# balanceador_arduino.net
KiCad netlist of a schematic drawn in EAGLE
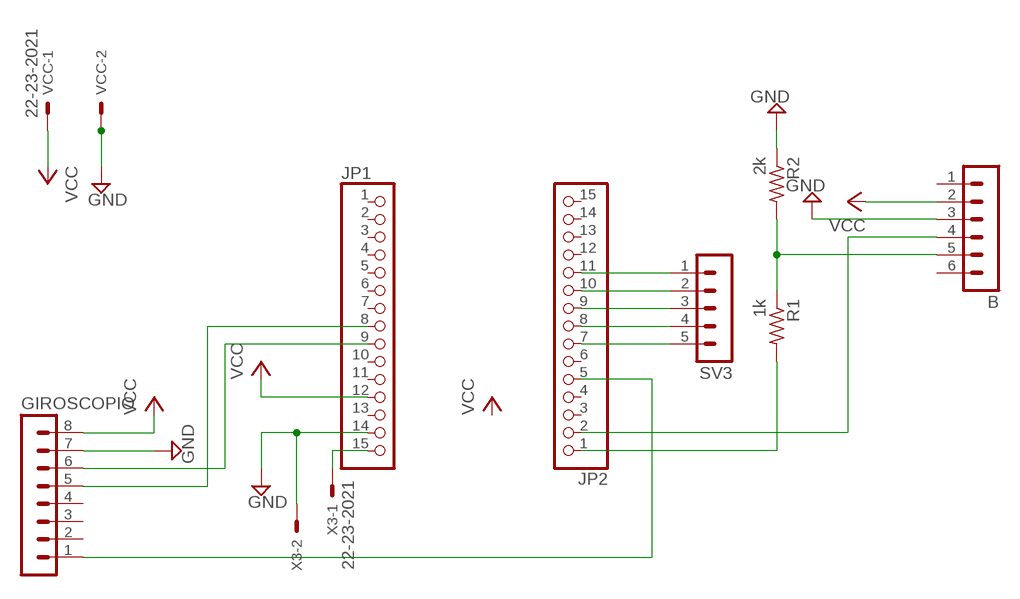
[diagram p0: schematic, sheet 1]

(export (version "E")
  (design (tool "Eeschema 10.0.6"))
  (components
    (comp (ref "B")
      (value "MA06-1")
      (footprint "eagle-import:MA06-1")
      (libsource (lib "eagle-import") (part "MA06-1"))
    )
    (comp (ref "GIROSCOPIO")
      (value "MA08-1")
      (footprint "eagle-import:MA08-1")
      (libsource (lib "eagle-import") (part "MA08-1"))
    )
    (comp (ref "JP1")
      (value "PINHD-1X15")
      (footprint "eagle-import:1X15")
      (libsource (lib "eagle-import") (part "PINHD-1X15"))
    )
    (comp (ref "JP2")
      (value "PINHD-1X15")
      (footprint "eagle-import:1X15")
      (libsource (lib "eagle-import") (part "PINHD-1X15"))
    )
    (comp (ref "R1")
      (value "1k")
      (footprint "eagle-import:0204_7")
      (libsource (lib "eagle-import") (part "R-US_0204/7"))
    )
    (comp (ref "R2")
      (value "2k")
      (footprint "eagle-import:0204_7")
      (libsource (lib "eagle-import") (part "R-US_0204/7"))
    )
    (comp (ref "SV3")
      (value "MA05-1")
      (footprint "eagle-import:MA05-1")
      (libsource (lib "eagle-import") (part "MA05-1"))
    )
    (comp (ref "VCC")
      (value "22-23-2021")
      (footprint "eagle-import:22-23-2021")
      (fields (field (name "MF") "MOLEX"))
      (libsource (lib "eagle-import") (part "22-23-2021"))
    )
    (comp (ref "X3")
      (value "22-23-2021")
      (footprint "eagle-import:22-23-2021")
      (fields (field (name "MF") "MOLEX"))
      (libsource (lib "eagle-import") (part "22-23-2021"))
    )
  )
  (nets
    (net (code "1") (name "GND") (class "Default")
      (node (ref "B") (pin "3") (pinfunction "3_3") (pintype "passive"))
      (node (ref "GIROSCOPIO") (pin "7") (pinfunction "7_7") (pintype "passive"))
      (node (ref "JP1") (pin "14") (pinfunction "14_14") (pintype "passive"))
      (node (ref "R2") (pin "1") (pinfunction "1_1") (pintype "passive"))
      (node (ref "VCC") (pin "2") (pinfunction "S_2") (pintype "passive"))
      (node (ref "X3") (pin "2") (pinfunction "S_2") (pintype "passive"))
    )
    (net (code "2") (name "Net-(B-Pad4)") (class "Default")
      (node (ref "B") (pin "4") (pinfunction "4_4") (pintype "passive"))
      (node (ref "JP2") (pin "2") (pinfunction "2_2") (pintype "passive"))
    )
    (net (code "3") (name "Net-(B-Pad5)") (class "Default")
      (node (ref "B") (pin "5") (pinfunction "5_5") (pintype "passive"))
      (node (ref "R1") (pin "1") (pinfunction "1_1") (pintype "passive"))
      (node (ref "R2") (pin "2") (pinfunction "2_2") (pintype "passive"))
    )
    (net (code "4") (name "Net-(GIROSCOPIO-Pad1)") (class "Default")
      (node (ref "GIROSCOPIO") (pin "1") (pinfunction "1_1") (pintype "passive"))
      (node (ref "JP2") (pin "5") (pinfunction "5_5") (pintype "passive"))
    )
    (net (code "5") (name "Net-(GIROSCOPIO-Pad5)") (class "Default")
      (node (ref "GIROSCOPIO") (pin "5") (pinfunction "5_5") (pintype "passive"))
      (node (ref "JP1") (pin "8") (pinfunction "8_8") (pintype "passive"))
    )
    (net (code "6") (name "Net-(GIROSCOPIO-Pad6)") (class "Default")
      (node (ref "GIROSCOPIO") (pin "6") (pinfunction "6_6") (pintype "passive"))
      (node (ref "JP1") (pin "9") (pinfunction "9_9") (pintype "passive"))
    )
    (net (code "7") (name "Net-(JP2-Pad1)") (class "Default")
      (node (ref "JP2") (pin "1") (pinfunction "1_1") (pintype "passive"))
      (node (ref "R1") (pin "2") (pinfunction "2_2") (pintype "passive"))
    )
    (net (code "8") (name "Net-(JP2-Pad7)") (class "Default")
      (node (ref "JP2") (pin "7") (pinfunction "7_7") (pintype "passive"))
      (node (ref "SV3") (pin "5") (pinfunction "5_5") (pintype "passive"))
    )
    (net (code "9") (name "Net-(JP2-Pad8)") (class "Default")
      (node (ref "JP2") (pin "8") (pinfunction "8_8") (pintype "passive"))
      (node (ref "SV3") (pin "4") (pinfunction "4_4") (pintype "passive"))
    )
    (net (code "10") (name "Net-(JP2-Pad9)") (class "Default")
      (node (ref "JP2") (pin "9") (pinfunction "9_9") (pintype "passive"))
      (node (ref "SV3") (pin "3") (pinfunction "3_3") (pintype "passive"))
    )
    (net (code "11") (name "Net-(JP2-Pad10)") (class "Default")
      (node (ref "JP2") (pin "10") (pinfunction "10_10") (pintype "passive"))
      (node (ref "SV3") (pin "2") (pinfunction "2_2") (pintype "passive"))
    )
    (net (code "12") (name "Net-(JP2-Pad11)") (class "Default")
      (node (ref "JP2") (pin "11") (pinfunction "11_11") (pintype "passive"))
      (node (ref "SV3") (pin "1") (pinfunction "1_1") (pintype "passive"))
    )
    (net (code "13") (name "Net-(X3A-S)") (class "Default")
      (node (ref "JP1") (pin "15") (pinfunction "15_15") (pintype "passive"))
      (node (ref "X3") (pin "1") (pinfunction "S_1") (pintype "passive"))
    )
    (net (code "14") (name "VCC") (class "Default")
      (node (ref "B") (pin "2") (pinfunction "2_2") (pintype "passive"))
      (node (ref "GIROSCOPIO") (pin "8") (pinfunction "8_8") (pintype "passive"))
      (node (ref "JP1") (pin "12") (pinfunction "12_12") (pintype "passive"))
      (node (ref "VCC") (pin "1") (pinfunction "S_1") (pintype "passive"))
    )
    (net (code "15") (name "unconnected-(B-Pad1)") (class "Default")
      (node (ref "B") (pin "1") (pinfunction "1_1") (pintype "passive"))
    )
    (net (code "16") (name "unconnected-(B-Pad6)") (class "Default")
      (node (ref "B") (pin "6") (pinfunction "6_6") (pintype "passive"))
    )
    (net (code "17") (name "unconnected-(GIROSCOPIO-Pad2)") (class "Default")
      (node (ref "GIROSCOPIO") (pin "2") (pinfunction "2_2") (pintype "passive"))
    )
    (net (code "18") (name "unconnected-(GIROSCOPIO-Pad3)") (class "Default")
      (node (ref "GIROSCOPIO") (pin "3") (pinfunction "3_3") (pintype "passive"))
    )
    (net (code "19") (name "unconnected-(GIROSCOPIO-Pad4)") (class "Default")
      (node (ref "GIROSCOPIO") (pin "4") (pinfunction "4_4") (pintype "passive"))
    )
    (net (code "20") (name "unconnected-(JP1-Pad1)") (class "Default")
      (node (ref "JP1") (pin "1") (pinfunction "1_1") (pintype "passive"))
    )
    (net (code "21") (name "unconnected-(JP1-Pad2)") (class "Default")
      (node (ref "JP1") (pin "2") (pinfunction "2_2") (pintype "passive"))
    )
    (net (code "22") (name "unconnected-(JP1-Pad3)") (class "Default")
      (node (ref "JP1") (pin "3") (pinfunction "3_3") (pintype "passive"))
    )
    (net (code "23") (name "unconnected-(JP1-Pad4)") (class "Default")
      (node (ref "JP1") (pin "4") (pinfunction "4_4") (pintype "passive"))
    )
    (net (code "24") (name "unconnected-(JP1-Pad5)") (class "Default")
      (node (ref "JP1") (pin "5") (pinfunction "5_5") (pintype "passive"))
    )
    (net (code "25") (name "unconnected-(JP1-Pad6)") (class "Default")
      (node (ref "JP1") (pin "6") (pinfunction "6_6") (pintype "passive"))
    )
    (net (code "26") (name "unconnected-(JP1-Pad7)") (class "Default")
      (node (ref "JP1") (pin "7") (pinfunction "7_7") (pintype "passive"))
    )
    (net (code "27") (name "unconnected-(JP1-Pad10)") (class "Default")
      (node (ref "JP1") (pin "10") (pinfunction "10_10") (pintype "passive"))
    )
    (net (code "28") (name "unconnected-(JP1-Pad11)") (class "Default")
      (node (ref "JP1") (pin "11") (pinfunction "11_11") (pintype "passive"))
    )
    (net (code "29") (name "unconnected-(JP1-Pad13)") (class "Default")
      (node (ref "JP1") (pin "13") (pinfunction "13_13") (pintype "passive"))
    )
    (net (code "30") (name "unconnected-(JP2-Pad3)") (class "Default")
      (node (ref "JP2") (pin "3") (pinfunction "3_3") (pintype "passive"))
    )
    (net (code "31") (name "unconnected-(JP2-Pad4)") (class "Default")
      (node (ref "JP2") (pin "4") (pinfunction "4_4") (pintype "passive"))
    )
    (net (code "32") (name "unconnected-(JP2-Pad6)") (class "Default")
      (node (ref "JP2") (pin "6") (pinfunction "6_6") (pintype "passive"))
    )
    (net (code "33") (name "unconnected-(JP2-Pad12)") (class "Default")
      (node (ref "JP2") (pin "12") (pinfunction "12_12") (pintype "passive"))
    )
    (net (code "34") (name "unconnected-(JP2-Pad13)") (class "Default")
      (node (ref "JP2") (pin "13") (pinfunction "13_13") (pintype "passive"))
    )
    (net (code "35") (name "unconnected-(JP2-Pad14)") (class "Default")
      (node (ref "JP2") (pin "14") (pinfunction "14_14") (pintype "passive"))
    )
    (net (code "36") (name "unconnected-(JP2-Pad15)") (class "Default")
      (node (ref "JP2") (pin "15") (pinfunction "15_15") (pintype "passive"))
    )
  )
)
